# QCopterFC_PWR_Sch.net
KiCad netlist of a schematic drawn in Altium Designer
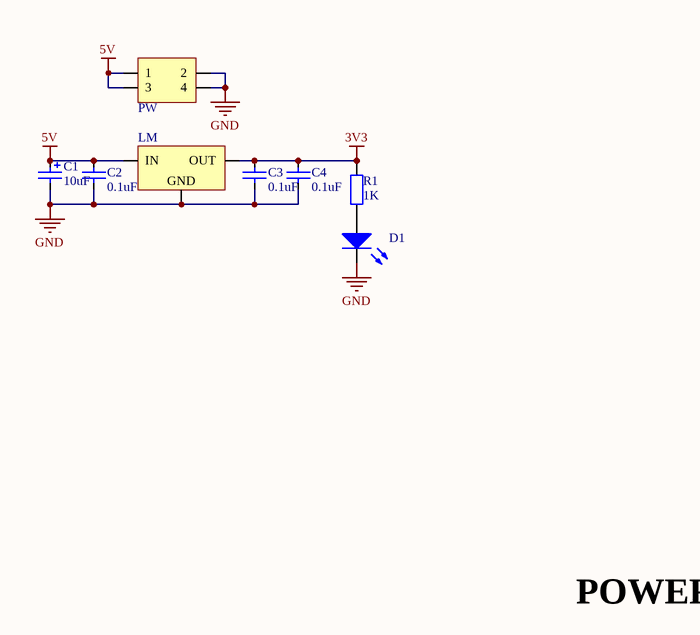
[diagram p0: QCopterFC_PWR_Sch.SchDoc]

(export (version "E")
  (design (tool "Eeschema 10.0.6"))
  (components
    (comp (ref "C1")
      (value "10uF")
      (footprint "PCB_Passive:CAP_TAN_B1210")
      (description "Capacitor")
      (fields (field (name "Comment") "Cap_Tan_1210"))
      (libsource (lib "SCH_Passive") (part "Cap_Tan_1210"))
    )
    (comp (ref "C2")
      (value "0.1uF")
      (footprint "PCB_Passive:CAP_0603")
      (description "Capacitor")
      (fields (field (name "Comment") "Cap_0603"))
      (libsource (lib "SCH_Passive") (part "Cap_0603"))
    )
    (comp (ref "C3")
      (value "0.1uF")
      (footprint "PCB_Passive:CAP_0603")
      (description "Capacitor")
      (fields (field (name "Comment") "Cap_0603"))
      (libsource (lib "SCH_Passive") (part "Cap_0603"))
    )
    (comp (ref "C4")
      (value "0.1uF")
      (footprint "PCB_Passive:CAP_0603")
      (description "Capacitor")
      (fields (field (name "Comment") "Cap_0603"))
      (libsource (lib "SCH_Passive") (part "Cap_0603"))
    )
    (comp (ref "D1")
      (value "LED_0603_BLUE")
      (footprint "PCB_Active:LED_0603_WHITE")
      (description "LED")
      (libsource (lib "SCH_Active") (part "LED_0603_BLUE"))
    )
    (comp (ref "LM")
      (value "LM1117")
      (footprint "PCB_IC:SOT223")
      (description "Power")
      (libsource (lib "SCH_IC") (part "LM1117"))
    )
    (comp (ref "PW")
      (value "HDR2X2_90_2.54")
      (footprint "PCB_Connector:HDR2X2_90_2.54")
      (description "Header")
      (libsource (lib "SCH_Connector") (part "HDR2X2_90_2.54"))
    )
    (comp (ref "R1")
      (value "1K")
      (footprint "PCB_Passive:RES_0603")
      (description "Resistor")
      (fields (field (name "Comment") "Res_0603"))
      (libsource (lib "SCH_Passive") (part "Res_0603"))
    )
  )
  (nets
    (net (code "1") (name "3V3") (class "Default")
      (node (ref "C3") (pin "2") (pinfunction "2_2") (pintype "passive"))
      (node (ref "C4") (pin "2") (pinfunction "2_2") (pintype "passive"))
      (node (ref "LM") (pin "2") (pinfunction "OUT_2") (pintype "power_in"))
      (node (ref "R1") (pin "2") (pinfunction "2_2") (pintype "passive"))
    )
    (net (code "2") (name "5V") (class "Default")
      (node (ref "C1") (pin "1") (pinfunction "1_1") (pintype "passive"))
      (node (ref "C2") (pin "2") (pinfunction "2_2") (pintype "passive"))
      (node (ref "LM") (pin "3") (pinfunction "IN_3") (pintype "power_in"))
      (node (ref "PW") (pin "1") (pinfunction "1_1") (pintype "passive"))
      (node (ref "PW") (pin "3") (pinfunction "3_3") (pintype "passive"))
    )
    (net (code "3") (name "GND") (class "Default")
      (node (ref "C1") (pin "2") (pinfunction "2_2") (pintype "passive"))
      (node (ref "C2") (pin "1") (pinfunction "1_1") (pintype "passive"))
      (node (ref "C3") (pin "1") (pinfunction "1_1") (pintype "passive"))
      (node (ref "C4") (pin "1") (pinfunction "1_1") (pintype "passive"))
      (node (ref "D1") (pin "2") (pinfunction "K_2") (pintype "passive"))
      (node (ref "LM") (pin "1") (pinfunction "GND_1") (pintype "power_in"))
      (node (ref "PW") (pin "2") (pinfunction "2_2") (pintype "passive"))
      (node (ref "PW") (pin "4") (pinfunction "4_4") (pintype "passive"))
    )
    (net (code "4") (name "Net-(D1-A)") (class "Default")
      (node (ref "D1") (pin "1") (pinfunction "A_1") (pintype "passive"))
      (node (ref "R1") (pin "1") (pinfunction "1_1") (pintype "passive"))
    )
  )
)
